# 2_18.net
KiCad netlist of a schematic drawn in EasyEDA Pro
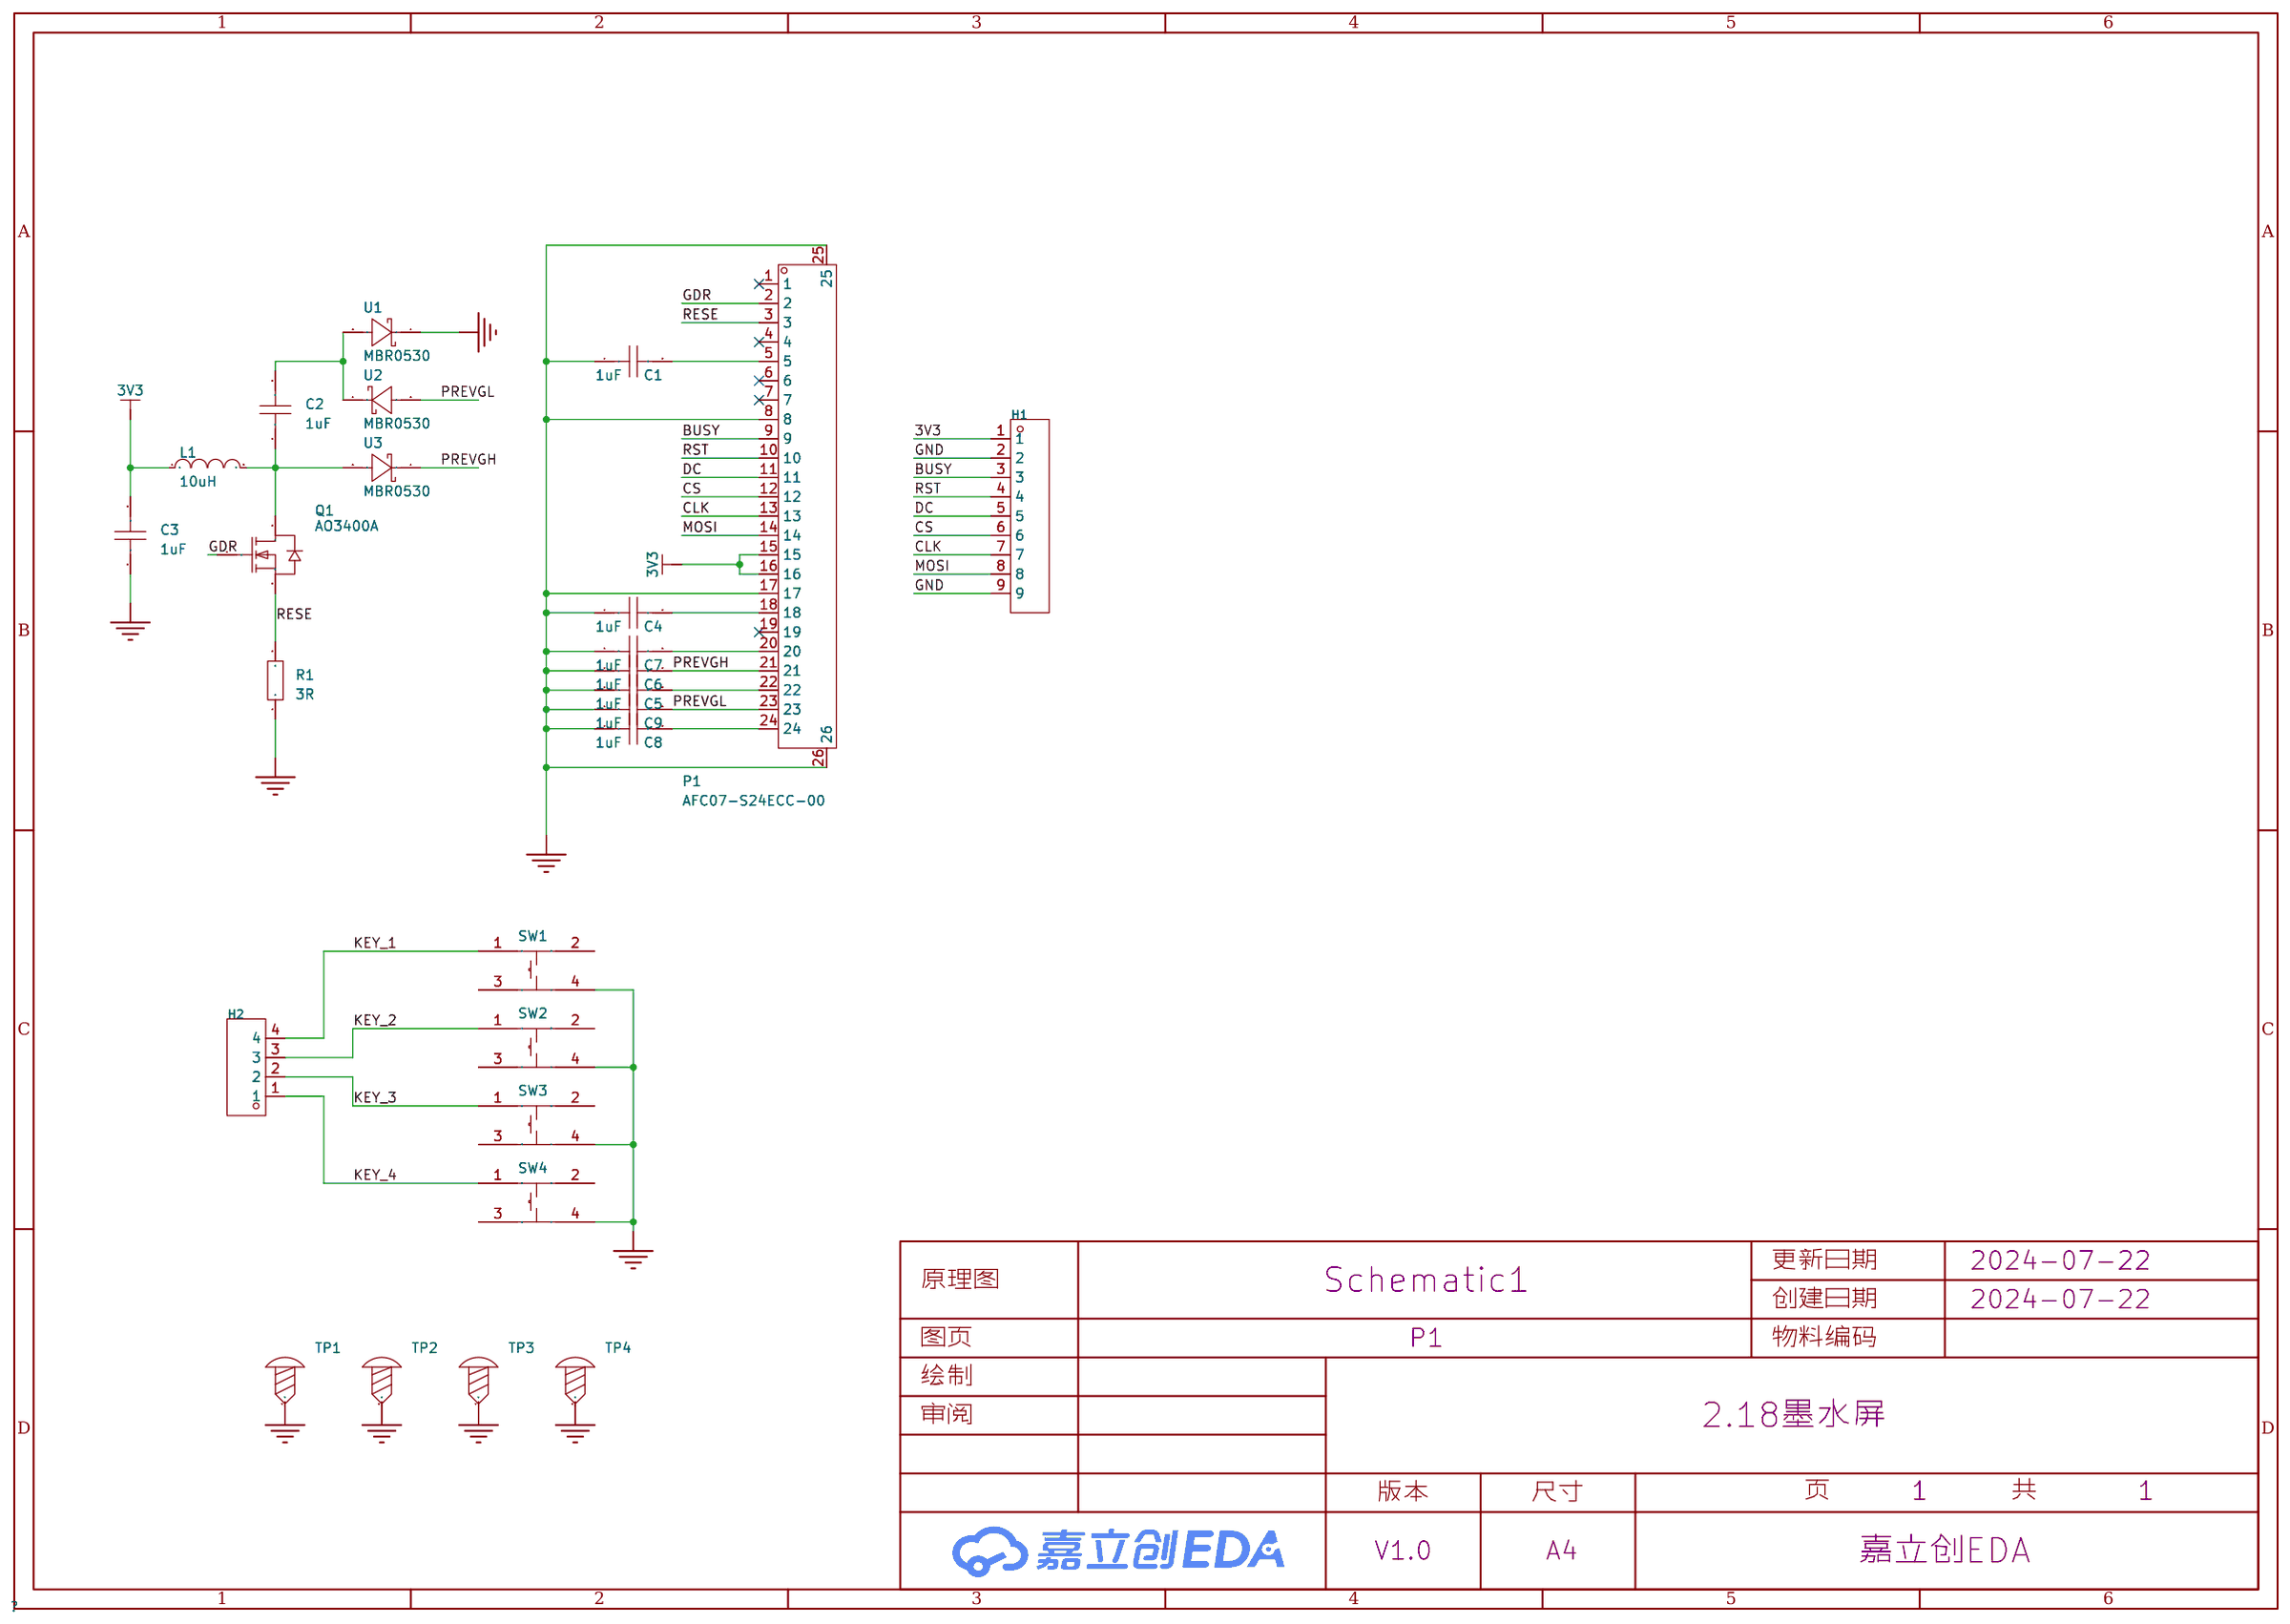
[diagram p0: schematic sheet]

(export (version "E")
  (design (tool "Eeschema 10.0.6"))
  (components
    (comp (ref "C1")
      (value "1uF")
      (footprint "easyedapro:C0603")
      (libsource (lib "easyedapro") (part "CapAcitance"))
    )
    (comp (ref "C2")
      (value "1uF")
      (footprint "easyedapro:C0603")
      (libsource (lib "easyedapro") (part "CapAcitance"))
    )
    (comp (ref "C3")
      (value "1uF")
      (footprint "easyedapro:C0603")
      (libsource (lib "easyedapro") (part "CapAcitance"))
    )
    (comp (ref "C4")
      (value "1uF")
      (footprint "easyedapro:C0603")
      (libsource (lib "easyedapro") (part "CapAcitance"))
    )
    (comp (ref "C5")
      (value "1uF")
      (footprint "easyedapro:C0603")
      (libsource (lib "easyedapro") (part "CapAcitance"))
    )
    (comp (ref "C6")
      (value "1uF")
      (footprint "easyedapro:C0603")
      (libsource (lib "easyedapro") (part "CapAcitance"))
    )
    (comp (ref "C7")
      (value "1uF")
      (footprint "easyedapro:C0603")
      (libsource (lib "easyedapro") (part "CapAcitance"))
    )
    (comp (ref "C8")
      (value "1uF")
      (footprint "easyedapro:C0603")
      (libsource (lib "easyedapro") (part "CapAcitance"))
    )
    (comp (ref "C9")
      (value "1uF")
      (footprint "easyedapro:C0603")
      (libsource (lib "easyedapro") (part "CapAcitance"))
    )
    (comp (ref "H1")
      (value "~")
      (footprint "easyedapro:HDR-TH_9P-P2.54-V-M")
      (libsource (lib "easyedapro") (part "PZ254V-11-09P"))
    )
    (comp (ref "H2")
      (value "~")
      (footprint "easyedapro:HDR-TH_4P-P2.54-V-M")
      (libsource (lib "easyedapro") (part "PZ254V-11-04P"))
    )
    (comp (ref "L1")
      (value "10uH")
      (footprint "easyedapro:L0805")
      (libsource (lib "easyedapro") (part "SDFL2012S100KTF"))
    )
    (comp (ref "P1")
      (value "AFC07-S24ECC-00")
      (footprint "easyedapro:FPC-SMD_24P-L17.5-W5.4-P0.50")
      (description "锁定特性:抽屉式;触点类型:上接;触点数量:24P;间距:0.5mm;安装类型:卧贴;")
      (fields (field (name "Manufacturer") "JS(钜硕电子)"))
      (libsource (lib "easyedapro") (part "FPC 0.5MM 24P Pull type H2.0mm Pick up"))
    )
    (comp (ref "Q1")
      (value "AO3400A")
      (footprint "easyedapro:SOT-23-3_L2.9-W1.6-P1.90-LS2.8-BR")
      (fields (field (name "Manufacturer") "AOS"))
      (libsource (lib "easyedapro") (part "AO3400A"))
    )
    (comp (ref "R1") (value "3R") (footprint "easyedapro:R0603") (libsource (lib "easyedapro") (part "电阻")))
    (comp (ref "SW1")
      (value "K2-1808SN-A3SW-01")
      (footprint "easyedapro:SW-SMD_4P-L4.2-W3.3-P2.15-LS5.1")
      (fields (field (name "Manufacturer") "韩国韩荣"))
      (libsource (lib "easyedapro") (part "K2-1808SN-A3SW-01"))
    )
    (comp (ref "SW2")
      (value "K2-1808SN-A3SW-01")
      (footprint "easyedapro:SW-SMD_4P-L4.2-W3.3-P2.15-LS5.1")
      (fields (field (name "Manufacturer") "韩国韩荣"))
      (libsource (lib "easyedapro") (part "K2-1808SN-A3SW-01"))
    )
    (comp (ref "SW3")
      (value "K2-1808SN-A3SW-01")
      (footprint "easyedapro:SW-SMD_4P-L4.2-W3.3-P2.15-LS5.1")
      (fields (field (name "Manufacturer") "韩国韩荣"))
      (libsource (lib "easyedapro") (part "K2-1808SN-A3SW-01"))
    )
    (comp (ref "SW4")
      (value "K2-1808SN-A3SW-01")
      (footprint "easyedapro:SW-SMD_4P-L4.2-W3.3-P2.15-LS5.1")
      (fields (field (name "Manufacturer") "韩国韩荣"))
      (libsource (lib "easyedapro") (part "K2-1808SN-A3SW-01"))
    )
    (comp (ref "TP1") (value "~") (footprint "easyedapro:M3螺丝") (libsource (lib "easyedapro") (part "螺丝孔")))
    (comp (ref "TP2") (value "~") (footprint "easyedapro:M3螺丝") (libsource (lib "easyedapro") (part "螺丝孔")))
    (comp (ref "TP3") (value "~") (footprint "easyedapro:M3螺丝") (libsource (lib "easyedapro") (part "螺丝孔")))
    (comp (ref "TP4") (value "~") (footprint "easyedapro:M3螺丝") (libsource (lib "easyedapro") (part "螺丝孔")))
    (comp (ref "U1")
      (value "MBR0530")
      (footprint "easyedapro:SOD-123_L2.7-W1.6-LS3.7-RD-1")
      (description "直流反向耐压(Vr)：30V 平均整流电流(Io)：500mA 正向压降(Vf)：550mV@500mA 30V,0.5A,VF=0.55V@0.5A")
      (fields (field (name "Manufacturer") "TWGMC(台湾迪嘉)"))
      (libsource (lib "easyedapro") (part "MBR0530_C5204746"))
    )
    (comp (ref "U2")
      (value "MBR0530")
      (footprint "easyedapro:SOD-123_L2.7-W1.6-LS3.7-RD-1")
      (description "直流反向耐压(Vr)：30V 平均整流电流(Io)：500mA 正向压降(Vf)：550mV@500mA 30V,0.5A,VF=0.55V@0.5A")
      (fields (field (name "Manufacturer") "TWGMC(台湾迪嘉)"))
      (libsource (lib "easyedapro") (part "MBR0530_C5204746"))
    )
    (comp (ref "U3")
      (value "MBR0530")
      (footprint "easyedapro:SOD-123_L2.7-W1.6-LS3.7-RD-1")
      (description "直流反向耐压(Vr)：30V 平均整流电流(Io)：500mA 正向压降(Vf)：550mV@500mA 30V,0.5A,VF=0.55V@0.5A")
      (fields (field (name "Manufacturer") "TWGMC(台湾迪嘉)"))
      (libsource (lib "easyedapro") (part "MBR0530_C5204746"))
    )
  )
  (nets
    (net (code "1") (name "/BUSY") (class "Default")
      (node (ref "H1") (pin "3") (pinfunction "3_3") (pintype "input"))
      (node (ref "P1") (pin "9") (pinfunction "9_9") (pintype "unspecified"))
    )
    (net (code "2") (name "/CLK") (class "Default")
      (node (ref "H1") (pin "7") (pinfunction "7_7") (pintype "input"))
      (node (ref "P1") (pin "13") (pinfunction "13_13") (pintype "unspecified"))
    )
    (net (code "3") (name "/CS") (class "Default")
      (node (ref "H1") (pin "6") (pinfunction "6_6") (pintype "input"))
      (node (ref "P1") (pin "12") (pinfunction "12_12") (pintype "unspecified"))
    )
    (net (code "4") (name "/DC") (class "Default")
      (node (ref "H1") (pin "5") (pinfunction "5_5") (pintype "input"))
      (node (ref "P1") (pin "11") (pinfunction "11_11") (pintype "unspecified"))
    )
    (net (code "5") (name "/GDR") (class "Default")
      (node (ref "P1") (pin "2") (pinfunction "2_2") (pintype "unspecified"))
      (node (ref "Q1") (pin "1") (pinfunction "G_1") (pintype "unspecified"))
    )
    (net (code "6") (name "/KEY_1") (class "Default")
      (node (ref "H2") (pin "4") (pinfunction "4_4") (pintype "input"))
      (node (ref "SW1") (pin "1") (pinfunction "1_1") (pintype "input"))
    )
    (net (code "7") (name "/KEY_2") (class "Default")
      (node (ref "H2") (pin "3") (pinfunction "3_3") (pintype "input"))
      (node (ref "SW2") (pin "1") (pinfunction "1_1") (pintype "input"))
    )
    (net (code "8") (name "/KEY_3") (class "Default")
      (node (ref "H2") (pin "2") (pinfunction "2_2") (pintype "input"))
      (node (ref "SW3") (pin "1") (pinfunction "1_1") (pintype "input"))
    )
    (net (code "9") (name "/KEY_4") (class "Default")
      (node (ref "H2") (pin "1") (pinfunction "1_1") (pintype "input"))
      (node (ref "SW4") (pin "1") (pinfunction "1_1") (pintype "input"))
    )
    (net (code "10") (name "/MOSI") (class "Default")
      (node (ref "H1") (pin "8") (pinfunction "8_8") (pintype "input"))
      (node (ref "P1") (pin "14") (pinfunction "14_14") (pintype "unspecified"))
    )
    (net (code "11") (name "/PREVGH") (class "Default")
      (node (ref "C6") (pin "2") (pinfunction "2_2") (pintype "input"))
      (node (ref "P1") (pin "21") (pinfunction "21_21") (pintype "unspecified"))
      (node (ref "U3") (pin "1") (pinfunction "K_1") (pintype "unspecified"))
    )
    (net (code "12") (name "/PREVGL") (class "Default")
      (node (ref "C9") (pin "2") (pinfunction "2_2") (pintype "input"))
      (node (ref "P1") (pin "23") (pinfunction "23_23") (pintype "unspecified"))
      (node (ref "U2") (pin "2") (pinfunction "A_2") (pintype "unspecified"))
    )
    (net (code "13") (name "/RESE") (class "Default")
      (node (ref "P1") (pin "3") (pinfunction "3_3") (pintype "unspecified"))
      (node (ref "Q1") (pin "2") (pinfunction "S_2") (pintype "unspecified"))
      (node (ref "R1") (pin "2") (pinfunction "2_2") (pintype "input"))
    )
    (net (code "14") (name "/RST") (class "Default")
      (node (ref "H1") (pin "4") (pinfunction "4_4") (pintype "input"))
      (node (ref "P1") (pin "10") (pinfunction "10_10") (pintype "unspecified"))
    )
    (net (code "15") (name "3V3") (class "Default")
      (node (ref "C3") (pin "2") (pinfunction "2_2") (pintype "input"))
      (node (ref "H1") (pin "1") (pinfunction "1_1") (pintype "input"))
      (node (ref "L1") (pin "1") (pinfunction "1_1") (pintype "input"))
      (node (ref "P1") (pin "15") (pinfunction "15_15") (pintype "unspecified"))
      (node (ref "P1") (pin "16") (pinfunction "16_16") (pintype "unspecified"))
    )
    (net (code "16") (name "GND") (class "Default")
      (node (ref "C1") (pin "1") (pinfunction "1_1") (pintype "input"))
      (node (ref "C3") (pin "1") (pinfunction "1_1") (pintype "input"))
      (node (ref "C4") (pin "1") (pinfunction "1_1") (pintype "input"))
      (node (ref "C5") (pin "1") (pinfunction "1_1") (pintype "input"))
      (node (ref "C6") (pin "1") (pinfunction "1_1") (pintype "input"))
      (node (ref "C7") (pin "1") (pinfunction "1_1") (pintype "input"))
      (node (ref "C8") (pin "1") (pinfunction "1_1") (pintype "input"))
      (node (ref "C9") (pin "1") (pinfunction "1_1") (pintype "input"))
      (node (ref "H1") (pin "2") (pinfunction "2_2") (pintype "input"))
      (node (ref "H1") (pin "9") (pinfunction "9_9") (pintype "input"))
      (node (ref "P1") (pin "17") (pinfunction "17_17") (pintype "unspecified"))
      (node (ref "P1") (pin "25") (pinfunction "25_25") (pintype "unspecified"))
      (node (ref "P1") (pin "26") (pinfunction "26_26") (pintype "unspecified"))
      (node (ref "P1") (pin "8") (pinfunction "8_8") (pintype "unspecified"))
      (node (ref "R1") (pin "1") (pinfunction "1_1") (pintype "input"))
      (node (ref "SW1") (pin "4") (pinfunction "4_4") (pintype "input"))
      (node (ref "SW2") (pin "4") (pinfunction "4_4") (pintype "input"))
      (node (ref "SW3") (pin "4") (pinfunction "4_4") (pintype "input"))
      (node (ref "SW4") (pin "4") (pinfunction "4_4") (pintype "input"))
      (node (ref "TP1") (pin "1") (pinfunction "1_1") (pintype "input"))
      (node (ref "TP2") (pin "1") (pinfunction "1_1") (pintype "input"))
      (node (ref "TP3") (pin "1") (pinfunction "1_1") (pintype "input"))
      (node (ref "TP4") (pin "1") (pinfunction "1_1") (pintype "input"))
      (node (ref "U1") (pin "1") (pinfunction "K_1") (pintype "unspecified"))
    )
    (net (code "17") (name "Net-(C1-Pad2)") (class "Default")
      (node (ref "C1") (pin "2") (pinfunction "2_2") (pintype "input"))
      (node (ref "P1") (pin "5") (pinfunction "5_5") (pintype "unspecified"))
    )
    (net (code "18") (name "Net-(C4-Pad2)") (class "Default")
      (node (ref "C4") (pin "2") (pinfunction "2_2") (pintype "input"))
      (node (ref "P1") (pin "18") (pinfunction "18_18") (pintype "unspecified"))
    )
    (net (code "19") (name "Net-(C5-Pad2)") (class "Default")
      (node (ref "C5") (pin "2") (pinfunction "2_2") (pintype "input"))
      (node (ref "P1") (pin "22") (pinfunction "22_22") (pintype "unspecified"))
    )
    (net (code "20") (name "Net-(C7-Pad2)") (class "Default")
      (node (ref "C7") (pin "2") (pinfunction "2_2") (pintype "input"))
      (node (ref "P1") (pin "20") (pinfunction "20_20") (pintype "unspecified"))
    )
    (net (code "21") (name "Net-(C8-Pad2)") (class "Default")
      (node (ref "C8") (pin "2") (pinfunction "2_2") (pintype "input"))
      (node (ref "P1") (pin "24") (pinfunction "24_24") (pintype "unspecified"))
    )
    (net (code "22") (name "Net-(Q1-D)") (class "Default")
      (node (ref "C2") (pin "1") (pinfunction "1_1") (pintype "input"))
      (node (ref "L1") (pin "2") (pinfunction "2_2") (pintype "input"))
      (node (ref "Q1") (pin "3") (pinfunction "D_3") (pintype "unspecified"))
      (node (ref "U3") (pin "2") (pinfunction "A_2") (pintype "unspecified"))
    )
    (net (code "23") (name "Net-(U1-A)") (class "Default")
      (node (ref "C2") (pin "2") (pinfunction "2_2") (pintype "input"))
      (node (ref "U1") (pin "2") (pinfunction "A_2") (pintype "unspecified"))
      (node (ref "U2") (pin "1") (pinfunction "K_1") (pintype "unspecified"))
    )
    (net (code "24") (name "unconnected-(P1-Pad1)") (class "Default")
      (node (ref "P1") (pin "1") (pinfunction "1_1") (pintype "unspecified+no_connect"))
    )
    (net (code "25") (name "unconnected-(P1-Pad4)") (class "Default")
      (node (ref "P1") (pin "4") (pinfunction "4_4") (pintype "unspecified+no_connect"))
    )
    (net (code "26") (name "unconnected-(P1-Pad6)") (class "Default")
      (node (ref "P1") (pin "6") (pinfunction "6_6") (pintype "unspecified+no_connect"))
    )
    (net (code "27") (name "unconnected-(P1-Pad7)") (class "Default")
      (node (ref "P1") (pin "7") (pinfunction "7_7") (pintype "unspecified+no_connect"))
    )
    (net (code "28") (name "unconnected-(P1-Pad19)") (class "Default")
      (node (ref "P1") (pin "19") (pinfunction "19_19") (pintype "unspecified+no_connect"))
    )
    (net (code "29") (name "unconnected-(SW1-Pad2)") (class "Default")
      (node (ref "SW1") (pin "2") (pinfunction "2_2") (pintype "input"))
    )
    (net (code "30") (name "unconnected-(SW1-Pad3)") (class "Default")
      (node (ref "SW1") (pin "3") (pinfunction "3_3") (pintype "input"))
    )
    (net (code "31") (name "unconnected-(SW2-Pad2)") (class "Default")
      (node (ref "SW2") (pin "2") (pinfunction "2_2") (pintype "input"))
    )
    (net (code "32") (name "unconnected-(SW2-Pad3)") (class "Default")
      (node (ref "SW2") (pin "3") (pinfunction "3_3") (pintype "input"))
    )
    (net (code "33") (name "unconnected-(SW3-Pad2)") (class "Default")
      (node (ref "SW3") (pin "2") (pinfunction "2_2") (pintype "input"))
    )
    (net (code "34") (name "unconnected-(SW3-Pad3)") (class "Default")
      (node (ref "SW3") (pin "3") (pinfunction "3_3") (pintype "input"))
    )
    (net (code "35") (name "unconnected-(SW4-Pad2)") (class "Default")
      (node (ref "SW4") (pin "2") (pinfunction "2_2") (pintype "input"))
    )
    (net (code "36") (name "unconnected-(SW4-Pad3)") (class "Default")
      (node (ref "SW4") (pin "3") (pinfunction "3_3") (pintype "input"))
    )
  )
)
